# bicicletta-power.net
KiCad netlist of a schematic drawn in EAGLE
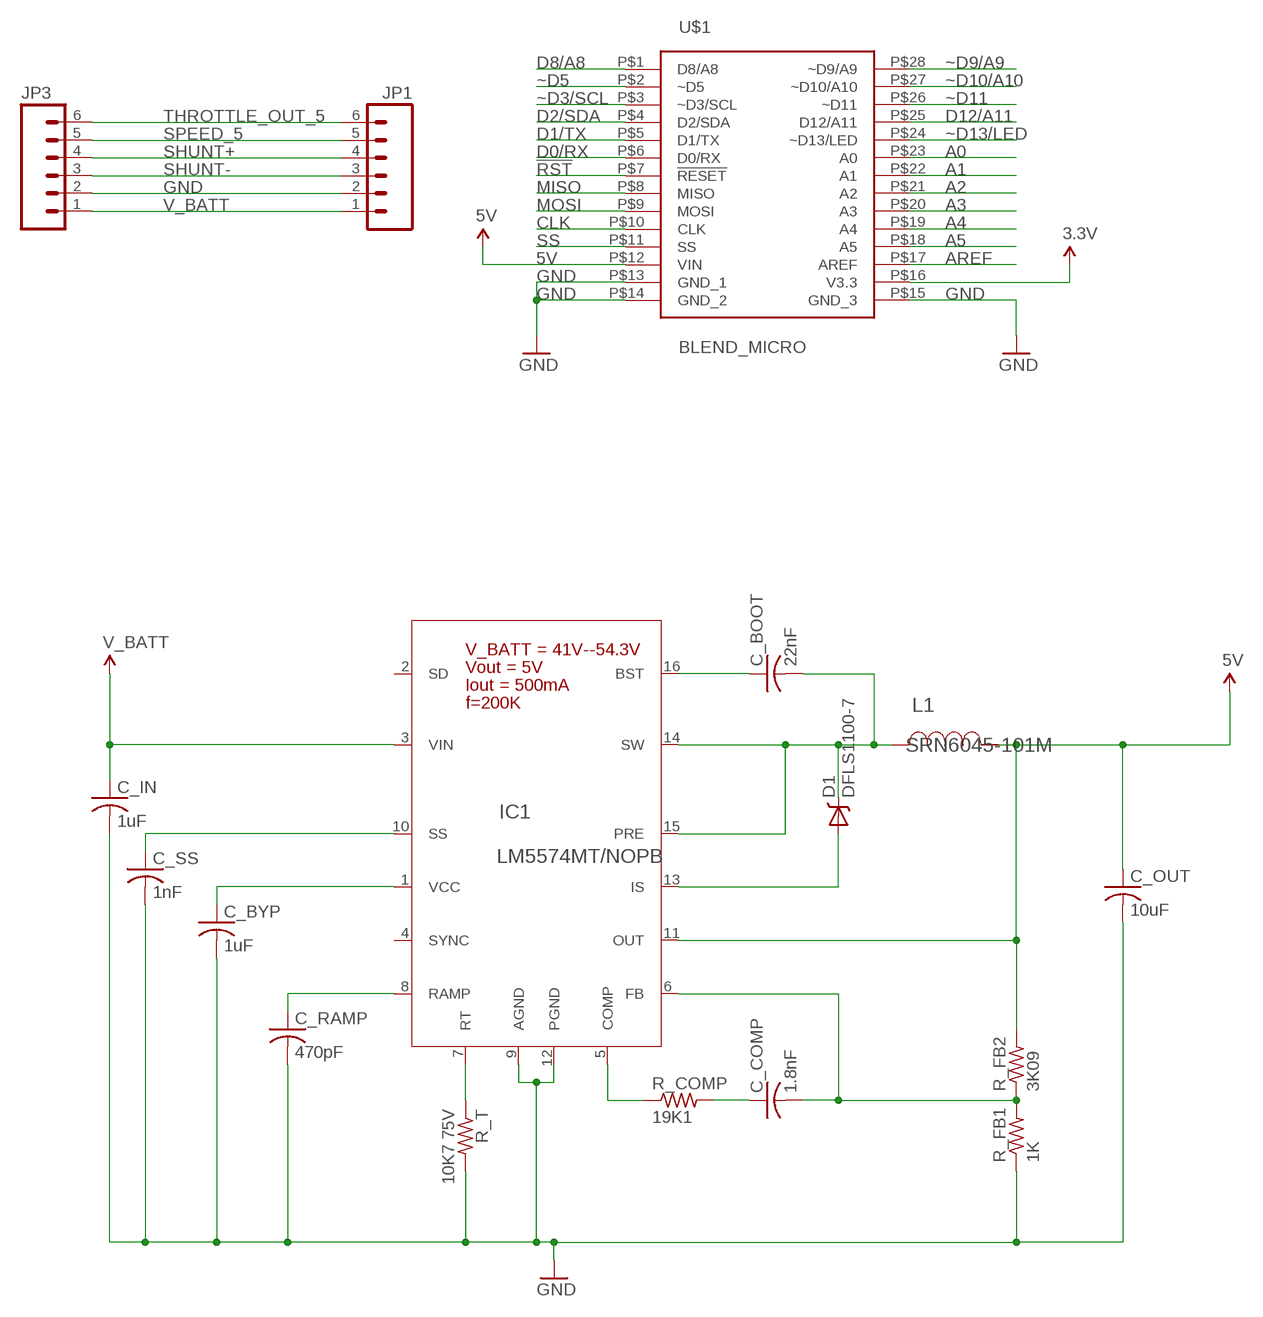
[diagram p0: schematic, sheet 1]

(export (version "E")
  (design (tool "Eeschema 10.0.6"))
  (components
    (comp (ref "C_BOOT")
      (value "22nF")
      (footprint "eagle-import:C0603")
      (libsource (lib "eagle-import") (part "C-USC0603"))
    )
    (comp (ref "C_BYP")
      (value "1uF")
      (footprint "eagle-import:C0603")
      (libsource (lib "eagle-import") (part "C-USC0603"))
    )
    (comp (ref "C_COMP")
      (value "1.8nF")
      (footprint "eagle-import:C0603")
      (libsource (lib "eagle-import") (part "C-USC0603"))
    )
    (comp (ref "C_IN")
      (value "1uF")
      (footprint "eagle-import:C1206")
      (libsource (lib "eagle-import") (part "C-USC1206"))
    )
    (comp (ref "C_OUT")
      (value "10uF")
      (footprint "eagle-import:C0805")
      (libsource (lib "eagle-import") (part "C-USC0805"))
    )
    (comp (ref "C_RAMP")
      (value "470pF")
      (footprint "eagle-import:C0603")
      (libsource (lib "eagle-import") (part "C-USC0603"))
    )
    (comp (ref "C_SS")
      (value "1nF")
      (footprint "eagle-import:C0603")
      (libsource (lib "eagle-import") (part "C-USC0603"))
    )
    (comp (ref "D1")
      (value "DFLS1100-7")
      (footprint "eagle-import:POWERDI123")
      (libsource (lib "eagle-import") (part "DFLS1100-7"))
    )
    (comp (ref "IC1")
      (value "LM5574MT/NOPB")
      (footprint "eagle-import:MTC16")
      (libsource (lib "eagle-import") (part "LM5574MT/NOPB"))
    )
    (comp (ref "JP1")
      (value "M06SIP")
      (footprint "eagle-import:1X06")
      (libsource (lib "eagle-import") (part "M06SIP"))
    )
    (comp (ref "JP3")
      (value "M06SIP")
      (footprint "eagle-import:1X06")
      (libsource (lib "eagle-import") (part "M06SIP"))
    )
    (comp (ref "L1")
      (value "SRN6045-101M")
      (footprint "eagle-import:SRN6045")
      (libsource (lib "eagle-import") (part "SRN6045-101M"))
    )
    (comp (ref "R_COMP")
      (value "19K1")
      (footprint "eagle-import:R0603")
      (libsource (lib "eagle-import") (part "R-US_R0603"))
    )
    (comp (ref "R_FB1")
      (value "1K")
      (footprint "eagle-import:R0603")
      (libsource (lib "eagle-import") (part "R-US_R0603"))
    )
    (comp (ref "R_FB2")
      (value "3K09")
      (footprint "eagle-import:R0603")
      (libsource (lib "eagle-import") (part "R-US_R0603"))
    )
    (comp (ref "R_T")
      (value "10K7 75V")
      (footprint "eagle-import:R0603")
      (libsource (lib "eagle-import") (part "R-US_R0603"))
    )
    (comp (ref "U$1")
      (value "BLEND_MICRO")
      (footprint "eagle-import:BLEND_MICRO")
      (libsource (lib "eagle-import") (part "BLEND_MICRO"))
    )
  )
  (nets
    (net (code "1") (name "/A0") (class "Default")
      (node (ref "U$1") (pin "P$23") (pinfunction "A0_P$23") (pintype "bidirectional"))
    )
    (net (code "2") (name "/A1") (class "Default")
      (node (ref "U$1") (pin "P$22") (pinfunction "A1_P$22") (pintype "bidirectional"))
    )
    (net (code "3") (name "/A2") (class "Default")
      (node (ref "U$1") (pin "P$21") (pinfunction "A2_P$21") (pintype "bidirectional"))
    )
    (net (code "4") (name "/A3") (class "Default")
      (node (ref "U$1") (pin "P$20") (pinfunction "A3_P$20") (pintype "bidirectional"))
    )
    (net (code "5") (name "/A4") (class "Default")
      (node (ref "U$1") (pin "P$19") (pinfunction "A4_P$19") (pintype "bidirectional"))
    )
    (net (code "6") (name "/A5") (class "Default")
      (node (ref "U$1") (pin "P$18") (pinfunction "A5_P$18") (pintype "bidirectional"))
    )
    (net (code "7") (name "/AREF") (class "Default")
      (node (ref "U$1") (pin "P$17") (pinfunction "AREF_P$17") (pintype "bidirectional"))
    )
    (net (code "8") (name "/CLK") (class "Default")
      (node (ref "U$1") (pin "P$10") (pinfunction "CLK_P$10") (pintype "bidirectional"))
    )
    (net (code "9") (name "/D0{slash}RX") (class "Default")
      (node (ref "U$1") (pin "P$6") (pinfunction "D0/RX_P$6") (pintype "bidirectional"))
    )
    (net (code "10") (name "/D1{slash}TX") (class "Default")
      (node (ref "U$1") (pin "P$5") (pinfunction "D1/TX_P$5") (pintype "bidirectional"))
    )
    (net (code "11") (name "/D2{slash}SDA") (class "Default")
      (node (ref "U$1") (pin "P$4") (pinfunction "D2/SDA_P$4") (pintype "bidirectional"))
    )
    (net (code "12") (name "/D8{slash}A8") (class "Default")
      (node (ref "U$1") (pin "P$1") (pinfunction "D8/A8_P$1") (pintype "bidirectional"))
    )
    (net (code "13") (name "/D12{slash}A11") (class "Default")
      (node (ref "U$1") (pin "P$25") (pinfunction "D12/A11_P$25") (pintype "bidirectional"))
    )
    (net (code "14") (name "/MISO") (class "Default")
      (node (ref "U$1") (pin "P$8") (pinfunction "MISO_P$8") (pintype "bidirectional"))
    )
    (net (code "15") (name "/MOSI") (class "Default")
      (node (ref "U$1") (pin "P$9") (pinfunction "MOSI_P$9") (pintype "bidirectional"))
    )
    (net (code "16") (name "/SHUNT+") (class "Default")
      (node (ref "JP1") (pin "4") (pinfunction "4_4") (pintype "passive"))
      (node (ref "JP3") (pin "4") (pinfunction "4_4") (pintype "passive"))
    )
    (net (code "17") (name "/SHUNT-") (class "Default")
      (node (ref "JP1") (pin "3") (pinfunction "3_3") (pintype "passive"))
      (node (ref "JP3") (pin "3") (pinfunction "3_3") (pintype "passive"))
    )
    (net (code "18") (name "/SPEED_5") (class "Default")
      (node (ref "JP1") (pin "5") (pinfunction "5_5") (pintype "passive"))
      (node (ref "JP3") (pin "5") (pinfunction "5_5") (pintype "passive"))
    )
    (net (code "19") (name "/SS") (class "Default")
      (node (ref "U$1") (pin "P$11") (pinfunction "SS_P$11") (pintype "bidirectional"))
    )
    (net (code "20") (name "/THROTTLE_OUT_5") (class "Default")
      (node (ref "JP1") (pin "6") (pinfunction "6_6") (pintype "passive"))
      (node (ref "JP3") (pin "6") (pinfunction "6_6") (pintype "passive"))
    )
    (net (code "21") (name "/~{D3{slash}SCL}") (class "Default")
      (node (ref "U$1") (pin "P$3") (pinfunction "~{D3/SCL}_P$3") (pintype "bidirectional"))
    )
    (net (code "22") (name "/~{D5}") (class "Default")
      (node (ref "U$1") (pin "P$2") (pinfunction "~{D5}_P$2") (pintype "bidirectional"))
    )
    (net (code "23") (name "/~{D9{slash}A9}") (class "Default")
      (node (ref "U$1") (pin "P$28") (pinfunction "~{D9/A9}_P$28") (pintype "bidirectional"))
    )
    (net (code "24") (name "/~{D10{slash}A10}") (class "Default")
      (node (ref "U$1") (pin "P$27") (pinfunction "~{D10/A10}_P$27") (pintype "bidirectional"))
    )
    (net (code "25") (name "/~{D11}") (class "Default")
      (node (ref "U$1") (pin "P$26") (pinfunction "~{D11}_P$26") (pintype "bidirectional"))
    )
    (net (code "26") (name "/~{D13{slash}LED}") (class "Default")
      (node (ref "U$1") (pin "P$24") (pinfunction "~{D13/LED}_P$24") (pintype "bidirectional"))
    )
    (net (code "27") (name "/~{RST}") (class "Default")
      (node (ref "U$1") (pin "P$7") (pinfunction "~{RESET}_P$7") (pintype "bidirectional"))
    )
    (net (code "28") (name "3.3V") (class "Default")
      (node (ref "U$1") (pin "P$16") (pinfunction "V3.3_P$16") (pintype "bidirectional"))
    )
    (net (code "29") (name "5V") (class "Default")
      (node (ref "C_OUT") (pin "1") (pinfunction "1_1") (pintype "passive"))
      (node (ref "IC1") (pin "11") (pinfunction "OUT_11") (pintype "passive"))
      (node (ref "L1") (pin "2") (pinfunction "2_2") (pintype "passive"))
      (node (ref "R_FB2") (pin "2") (pinfunction "2_2") (pintype "passive"))
      (node (ref "U$1") (pin "P$12") (pinfunction "VIN_P$12") (pintype "bidirectional"))
    )
    (net (code "30") (name "GND") (class "Default")
      (node (ref "C_BYP") (pin "2") (pinfunction "2_2") (pintype "passive"))
      (node (ref "C_IN") (pin "2") (pinfunction "2_2") (pintype "passive"))
      (node (ref "C_OUT") (pin "2") (pinfunction "2_2") (pintype "passive"))
      (node (ref "C_RAMP") (pin "2") (pinfunction "2_2") (pintype "passive"))
      (node (ref "C_SS") (pin "2") (pinfunction "2_2") (pintype "passive"))
      (node (ref "IC1") (pin "12") (pinfunction "PGND_12") (pintype "passive"))
      (node (ref "IC1") (pin "9") (pinfunction "AGND_9") (pintype "passive"))
      (node (ref "JP1") (pin "2") (pinfunction "2_2") (pintype "passive"))
      (node (ref "JP3") (pin "2") (pinfunction "2_2") (pintype "passive"))
      (node (ref "R_FB1") (pin "1") (pinfunction "1_1") (pintype "passive"))
      (node (ref "R_T") (pin "2") (pinfunction "2_2") (pintype "passive"))
      (node (ref "U$1") (pin "P$13") (pinfunction "GND_1_P$13") (pintype "bidirectional"))
      (node (ref "U$1") (pin "P$14") (pinfunction "GND_2_P$14") (pintype "bidirectional"))
      (node (ref "U$1") (pin "P$15") (pinfunction "GND_3_P$15") (pintype "bidirectional"))
    )
    (net (code "31") (name "Net-(C_COMP-Pad1)") (class "Default")
      (node (ref "C_COMP") (pin "1") (pinfunction "1_1") (pintype "passive"))
      (node (ref "R_COMP") (pin "2") (pinfunction "2_2") (pintype "passive"))
    )
    (net (code "32") (name "Net-(IC1-BST)") (class "Default")
      (node (ref "C_BOOT") (pin "1") (pinfunction "1_1") (pintype "passive"))
      (node (ref "IC1") (pin "16") (pinfunction "BST_16") (pintype "passive"))
    )
    (net (code "33") (name "Net-(IC1-COMP)") (class "Default")
      (node (ref "IC1") (pin "5") (pinfunction "COMP_5") (pintype "passive"))
      (node (ref "R_COMP") (pin "1") (pinfunction "1_1") (pintype "passive"))
    )
    (net (code "34") (name "Net-(IC1-FB)") (class "Default")
      (node (ref "C_COMP") (pin "2") (pinfunction "2_2") (pintype "passive"))
      (node (ref "IC1") (pin "6") (pinfunction "FB_6") (pintype "passive"))
      (node (ref "R_FB1") (pin "2") (pinfunction "2_2") (pintype "passive"))
      (node (ref "R_FB2") (pin "1") (pinfunction "1_1") (pintype "passive"))
    )
    (net (code "35") (name "Net-(IC1-IS)") (class "Default")
      (node (ref "D1") (pin "A") (pinfunction "A_A") (pintype "passive"))
      (node (ref "IC1") (pin "13") (pinfunction "IS_13") (pintype "passive"))
    )
    (net (code "36") (name "Net-(IC1-PRE)") (class "Default")
      (node (ref "C_BOOT") (pin "2") (pinfunction "2_2") (pintype "passive"))
      (node (ref "D1") (pin "K") (pinfunction "K_K") (pintype "passive"))
      (node (ref "IC1") (pin "14") (pinfunction "SW_14") (pintype "passive"))
      (node (ref "IC1") (pin "15") (pinfunction "PRE_15") (pintype "passive"))
      (node (ref "L1") (pin "1") (pinfunction "1_1") (pintype "passive"))
    )
    (net (code "37") (name "Net-(IC1-RAMP)") (class "Default")
      (node (ref "C_RAMP") (pin "1") (pinfunction "1_1") (pintype "passive"))
      (node (ref "IC1") (pin "8") (pinfunction "RAMP_8") (pintype "passive"))
    )
    (net (code "38") (name "Net-(IC1-RT)") (class "Default")
      (node (ref "IC1") (pin "7") (pinfunction "RT_7") (pintype "passive"))
      (node (ref "R_T") (pin "1") (pinfunction "1_1") (pintype "passive"))
    )
    (net (code "39") (name "Net-(IC1-SS)") (class "Default")
      (node (ref "C_SS") (pin "1") (pinfunction "1_1") (pintype "passive"))
      (node (ref "IC1") (pin "10") (pinfunction "SS_10") (pintype "passive"))
    )
    (net (code "40") (name "Net-(IC1-VCC)") (class "Default")
      (node (ref "C_BYP") (pin "1") (pinfunction "1_1") (pintype "passive"))
      (node (ref "IC1") (pin "1") (pinfunction "VCC_1") (pintype "passive"))
    )
    (net (code "41") (name "V_BATT") (class "Default")
      (node (ref "C_IN") (pin "1") (pinfunction "1_1") (pintype "passive"))
      (node (ref "IC1") (pin "3") (pinfunction "VIN_3") (pintype "passive"))
      (node (ref "JP1") (pin "1") (pinfunction "1_1") (pintype "passive"))
      (node (ref "JP3") (pin "1") (pinfunction "1_1") (pintype "passive"))
    )
    (net (code "42") (name "unconnected-(IC1-SD-Pad2)") (class "Default")
      (node (ref "IC1") (pin "2") (pinfunction "SD_2") (pintype "passive"))
    )
    (net (code "43") (name "unconnected-(IC1-SYNC-Pad4)") (class "Default")
      (node (ref "IC1") (pin "4") (pinfunction "SYNC_4") (pintype "passive"))
    )
  )
)
